# PulseFit.net
KiCad netlist of a schematic drawn in EAGLE
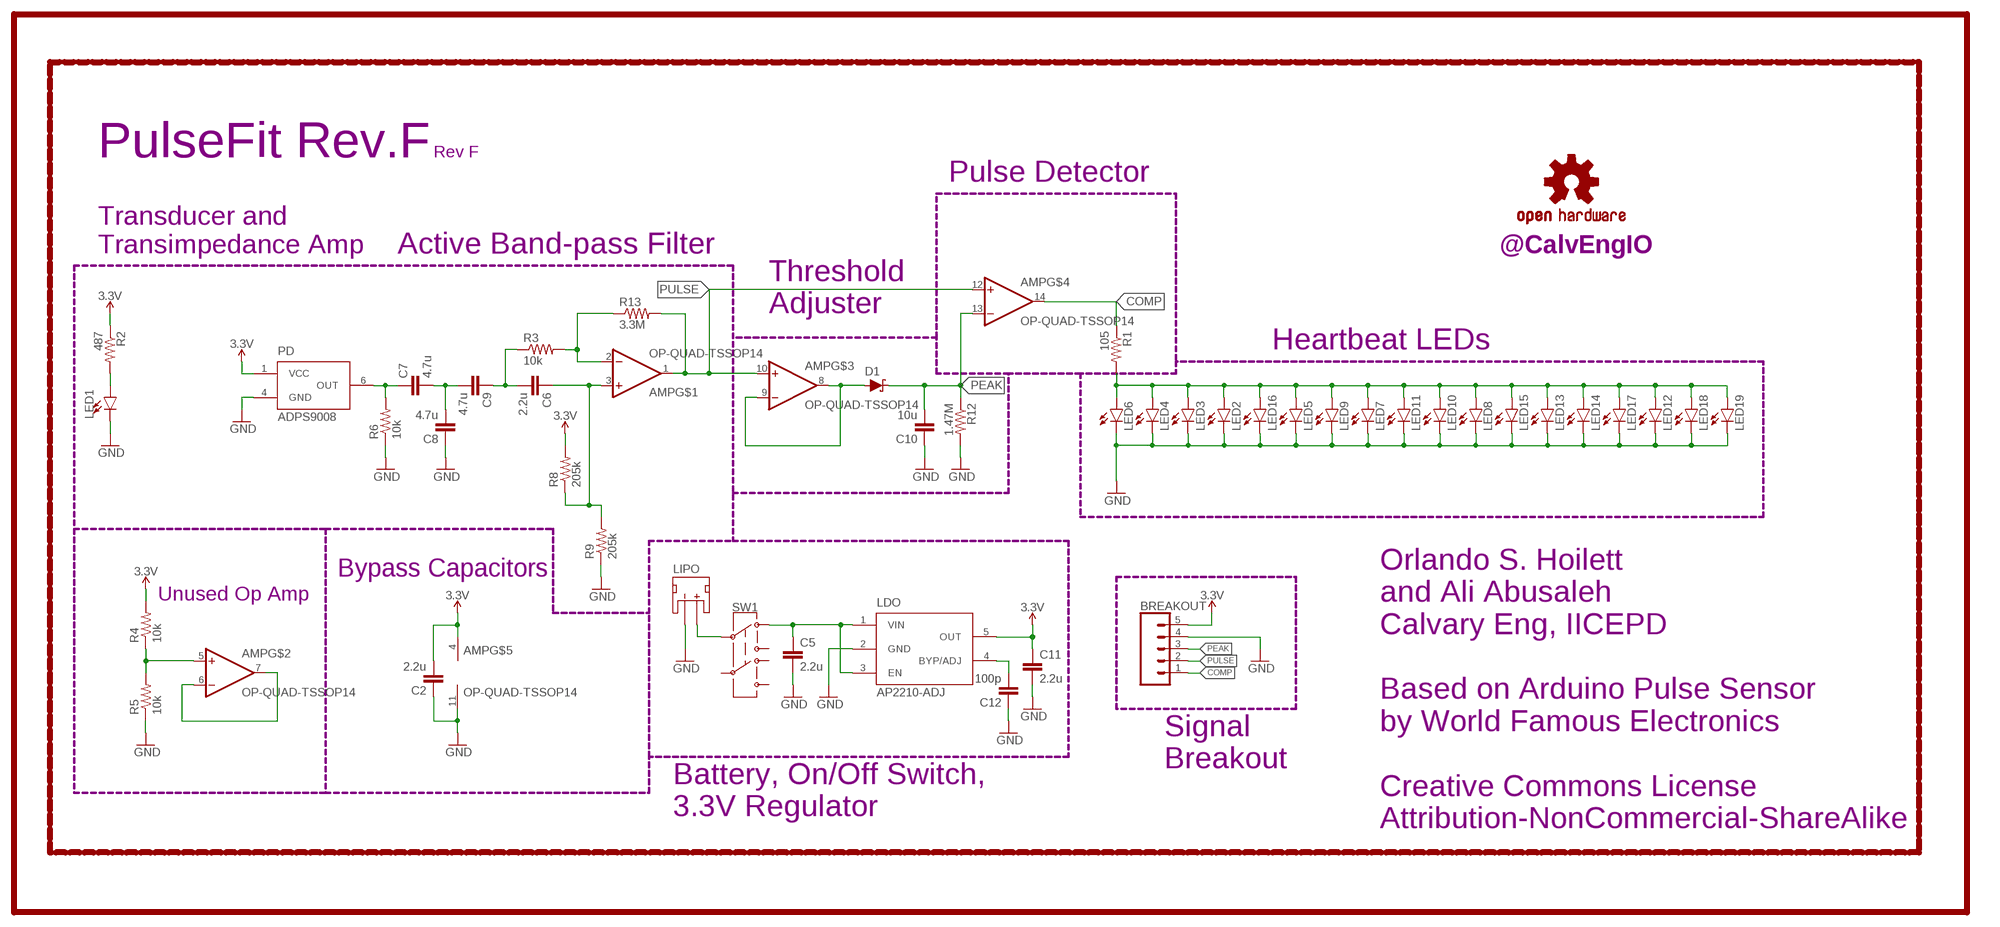
[diagram p0: schematic, sheet 1]

(export (version "E")
  (design (tool "Eeschema 10.0.6"))
  (components
    (comp (ref "AMP")
      (value "OP-QUAD-TSSOP14")
      (footprint "eagle-import:TSSOP14")
      (libsource (lib "eagle-import") (part "OP-QUAD-TSSOP14"))
    )
    (comp (ref "BREAKOUT")
      (value "CONN_05NO_SILK")
      (footprint "eagle-import:1X05_NO_SILK")
      (libsource (lib "eagle-import") (part "CONN_05NO_SILK"))
    )
    (comp (ref "C2")
      (value "2.2u")
      (footprint "eagle-import:C0402")
      (libsource (lib "eagle-import") (part "CAPACITOR0402"))
    )
    (comp (ref "C5")
      (value "2.2u")
      (footprint "eagle-import:C0603")
      (libsource (lib "eagle-import") (part "CAPACITOR0603"))
    )
    (comp (ref "C6")
      (value "2.2u")
      (footprint "eagle-import:C0603")
      (libsource (lib "eagle-import") (part "CAPACITOR0603"))
    )
    (comp (ref "C7")
      (value "4.7u")
      (footprint "eagle-import:C0603")
      (libsource (lib "eagle-import") (part "CAPACITOR0603"))
    )
    (comp (ref "C8")
      (value "4.7u")
      (footprint "eagle-import:C0603")
      (libsource (lib "eagle-import") (part "CAPACITOR0603"))
    )
    (comp (ref "C9")
      (value "4.7u")
      (footprint "eagle-import:C0603")
      (libsource (lib "eagle-import") (part "CAPACITOR0603"))
    )
    (comp (ref "C10")
      (value "10u")
      (footprint "eagle-import:C0805")
      (libsource (lib "eagle-import") (part "CAPACITOR0805"))
    )
    (comp (ref "C11")
      (value "2.2u")
      (footprint "eagle-import:C0603")
      (libsource (lib "eagle-import") (part "CAPACITOR0603"))
    )
    (comp (ref "C12")
      (value "100p")
      (footprint "eagle-import:C0402")
      (libsource (lib "eagle-import") (part "CAPACITOR0402"))
    )
    (comp (ref "D1")
      (value "SCHOTTKY-USC")
      (footprint "eagle-import:USC")
      (libsource (lib "eagle-import") (part "SCHOTTKY-USC"))
    )
    (comp (ref "LDO")
      (value "AP2210-ADJ")
      (footprint "eagle-import:SOT23-5")
      (libsource (lib "eagle-import") (part "AP2210-ADJ"))
    )
    (comp (ref "LED1")
      (value "LEDZ-BEND")
      (footprint "eagle-import:2-SMD.Z-BEND")
      (libsource (lib "eagle-import") (part "LEDZ-BEND"))
    )
    (comp (ref "LED2")
      (value "LED5MM")
      (footprint "eagle-import:LED5MM")
      (libsource (lib "eagle-import") (part "SparkFun-LED_LED5MM"))
    )
    (comp (ref "LED3")
      (value "LED5MM")
      (footprint "eagle-import:LED5MM")
      (libsource (lib "eagle-import") (part "SparkFun-LED_LED5MM"))
    )
    (comp (ref "LED4")
      (value "LED5MM")
      (footprint "eagle-import:LED5MM")
      (libsource (lib "eagle-import") (part "SparkFun-LED_LED5MM"))
    )
    (comp (ref "LED5")
      (value "LED5MM")
      (footprint "eagle-import:LED5MM")
      (libsource (lib "eagle-import") (part "SparkFun-LED_LED5MM"))
    )
    (comp (ref "LED6")
      (value "LED5MM")
      (footprint "eagle-import:LED5MM")
      (libsource (lib "eagle-import") (part "SparkFun-LED_LED5MM"))
    )
    (comp (ref "LED7")
      (value "LED5MM")
      (footprint "eagle-import:LED5MM")
      (libsource (lib "eagle-import") (part "SparkFun-LED_LED5MM"))
    )
    (comp (ref "LED8")
      (value "LED5MM")
      (footprint "eagle-import:LED5MM")
      (libsource (lib "eagle-import") (part "SparkFun-LED_LED5MM"))
    )
    (comp (ref "LED9")
      (value "LED5MM")
      (footprint "eagle-import:LED5MM")
      (libsource (lib "eagle-import") (part "SparkFun-LED_LED5MM"))
    )
    (comp (ref "LED10")
      (value "LED5MM")
      (footprint "eagle-import:LED5MM")
      (libsource (lib "eagle-import") (part "SparkFun-LED_LED5MM"))
    )
    (comp (ref "LED11")
      (value "LED5MM")
      (footprint "eagle-import:LED5MM")
      (libsource (lib "eagle-import") (part "SparkFun-LED_LED5MM"))
    )
    (comp (ref "LED12")
      (value "LED5MM")
      (footprint "eagle-import:LED5MM")
      (libsource (lib "eagle-import") (part "SparkFun-LED_LED5MM"))
    )
    (comp (ref "LED13")
      (value "LED5MM")
      (footprint "eagle-import:LED5MM")
      (libsource (lib "eagle-import") (part "SparkFun-LED_LED5MM"))
    )
    (comp (ref "LED14")
      (value "LED5MM")
      (footprint "eagle-import:LED5MM")
      (libsource (lib "eagle-import") (part "SparkFun-LED_LED5MM"))
    )
    (comp (ref "LED15")
      (value "LED5MM")
      (footprint "eagle-import:LED5MM")
      (libsource (lib "eagle-import") (part "SparkFun-LED_LED5MM"))
    )
    (comp (ref "LED16")
      (value "LED5MM")
      (footprint "eagle-import:LED5MM")
      (libsource (lib "eagle-import") (part "SparkFun-LED_LED5MM"))
    )
    (comp (ref "LED17")
      (value "LED5MM")
      (footprint "eagle-import:LED5MM")
      (libsource (lib "eagle-import") (part "SparkFun-LED_LED5MM"))
    )
    (comp (ref "LED18")
      (value "LED5MM")
      (footprint "eagle-import:LED5MM")
      (libsource (lib "eagle-import") (part "SparkFun-LED_LED5MM"))
    )
    (comp (ref "LED19")
      (value "LED5MM")
      (footprint "eagle-import:LED5MM")
      (libsource (lib "eagle-import") (part "SparkFun-LED_LED5MM"))
    )
    (comp (ref "LIPO")
      (value "JST_2MM_MALE")
      (footprint "eagle-import:JST-2-SMD")
      (libsource (lib "eagle-import") (part "JST_2MM_MALE"))
    )
    (comp (ref "LOGO1")
      (value "OSHW-LOGOS")
      (footprint "eagle-import:OSHW-LOGO-S")
      (libsource (lib "eagle-import") (part "OSHW-LOGOS"))
    )
    (comp (ref "PD")
      (value "ADPS9008")
      (footprint "eagle-import:6-PIN.CHIPLED")
      (libsource (lib "eagle-import") (part "ADPS9008"))
    )
    (comp (ref "R1")
      (value "105")
      (footprint "eagle-import:R0402")
      (libsource (lib "eagle-import") (part "RESISTOR0402"))
    )
    (comp (ref "R2")
      (value "487")
      (footprint "eagle-import:R0402")
      (libsource (lib "eagle-import") (part "RESISTOR0402"))
    )
    (comp (ref "R3")
      (value "10k")
      (footprint "eagle-import:R0402")
      (libsource (lib "eagle-import") (part "RESISTOR0402"))
    )
    (comp (ref "R4")
      (value "10k")
      (footprint "eagle-import:R0402")
      (libsource (lib "eagle-import") (part "RESISTOR0402"))
    )
    (comp (ref "R5")
      (value "10k")
      (footprint "eagle-import:R0402")
      (libsource (lib "eagle-import") (part "RESISTOR0402"))
    )
    (comp (ref "R6")
      (value "10k")
      (footprint "eagle-import:R0402")
      (libsource (lib "eagle-import") (part "RESISTOR0402"))
    )
    (comp (ref "R8")
      (value "205k")
      (footprint "eagle-import:R0402")
      (libsource (lib "eagle-import") (part "RESISTOR0402"))
    )
    (comp (ref "R9")
      (value "205k")
      (footprint "eagle-import:R0402")
      (libsource (lib "eagle-import") (part "RESISTOR0402"))
    )
    (comp (ref "R12")
      (value "1.47M")
      (footprint "eagle-import:R0402")
      (libsource (lib "eagle-import") (part "RESISTOR0402"))
    )
    (comp (ref "R13")
      (value "3.3M")
      (footprint "eagle-import:R0402")
      (libsource (lib "eagle-import") (part "RESISTOR0402"))
    )
    (comp (ref "SW1")
      (value "SWITCH.JS202011JCQN")
      (footprint "eagle-import:SWITCH.00")
      (libsource (lib "eagle-import") (part "SWITCH.JS202011JCQN"))
    )
    (comp (ref "U$1")
      (value "CALVENGIO_HANDLEHANDLE.05")
      (footprint "eagle-import:CALVENGIO_HANDLE.05")
      (libsource (lib "eagle-import") (part "CALVENGIO_HANDLEHANDLE.05"))
    )
    (comp (ref "U$2")
      (value "REVISION.F")
      (footprint "eagle-import:REV.F")
      (libsource (lib "eagle-import") (part "REVISION.F"))
    )
  )
  (nets
    (net (code "1") (name "3.3V") (class "Default")
      (node (ref "AMP") (pin "4") (pinfunction "V+_4") (pintype "power_in"))
      (node (ref "BREAKOUT") (pin "5") (pinfunction "5_5") (pintype "passive"))
      (node (ref "C11") (pin "1") (pinfunction "1_1") (pintype "passive"))
      (node (ref "C2") (pin "2") (pinfunction "2_2") (pintype "passive"))
      (node (ref "LDO") (pin "5") (pinfunction "OUT_5") (pintype "bidirectional"))
      (node (ref "PD") (pin "1") (pinfunction "VCC_1") (pintype "bidirectional"))
      (node (ref "R2") (pin "1") (pinfunction "1_1") (pintype "passive"))
      (node (ref "R4") (pin "2") (pinfunction "2_2") (pintype "passive"))
      (node (ref "R8") (pin "2") (pinfunction "2_2") (pintype "passive"))
    )
    (net (code "2") (name "COMP") (class "Default")
      (node (ref "AMP") (pin "14") (pinfunction "OUT_14") (pintype "output"))
      (node (ref "BREAKOUT") (pin "1") (pinfunction "1_1") (pintype "passive"))
      (node (ref "R1") (pin "1") (pinfunction "1_1") (pintype "passive"))
    )
    (net (code "3") (name "GND") (class "Default")
      (node (ref "AMP") (pin "11") (pinfunction "V-_11") (pintype "power_in"))
      (node (ref "BREAKOUT") (pin "4") (pinfunction "4_4") (pintype "passive"))
      (node (ref "C10") (pin "1") (pinfunction "1_1") (pintype "passive"))
      (node (ref "C11") (pin "2") (pinfunction "2_2") (pintype "passive"))
      (node (ref "C12") (pin "1") (pinfunction "1_1") (pintype "passive"))
      (node (ref "C2") (pin "1") (pinfunction "1_1") (pintype "passive"))
      (node (ref "C5") (pin "2") (pinfunction "2_2") (pintype "passive"))
      (node (ref "C8") (pin "1") (pinfunction "1_1") (pintype "passive"))
      (node (ref "LDO") (pin "2") (pinfunction "GND_2") (pintype "bidirectional"))
      (node (ref "LED1") (pin "-") (pinfunction "C_-") (pintype "passive"))
      (node (ref "LED10") (pin "K") (pinfunction "C_K") (pintype "passive"))
      (node (ref "LED11") (pin "K") (pinfunction "C_K") (pintype "passive"))
      (node (ref "LED12") (pin "K") (pinfunction "C_K") (pintype "passive"))
      (node (ref "LED13") (pin "K") (pinfunction "C_K") (pintype "passive"))
      (node (ref "LED14") (pin "K") (pinfunction "C_K") (pintype "passive"))
      (node (ref "LED15") (pin "K") (pinfunction "C_K") (pintype "passive"))
      (node (ref "LED16") (pin "K") (pinfunction "C_K") (pintype "passive"))
      (node (ref "LED17") (pin "K") (pinfunction "C_K") (pintype "passive"))
      (node (ref "LED18") (pin "K") (pinfunction "C_K") (pintype "passive"))
      (node (ref "LED19") (pin "K") (pinfunction "C_K") (pintype "passive"))
      (node (ref "LED2") (pin "K") (pinfunction "C_K") (pintype "passive"))
      (node (ref "LED3") (pin "K") (pinfunction "C_K") (pintype "passive"))
      (node (ref "LED4") (pin "K") (pinfunction "C_K") (pintype "passive"))
      (node (ref "LED5") (pin "K") (pinfunction "C_K") (pintype "passive"))
      (node (ref "LED6") (pin "K") (pinfunction "C_K") (pintype "passive"))
      (node (ref "LED7") (pin "K") (pinfunction "C_K") (pintype "passive"))
      (node (ref "LED8") (pin "K") (pinfunction "C_K") (pintype "passive"))
      (node (ref "LED9") (pin "K") (pinfunction "C_K") (pintype "passive"))
      (node (ref "LIPO") (pin "1") (pinfunction "-_1") (pintype "bidirectional"))
      (node (ref "PD") (pin "4") (pinfunction "GND_4") (pintype "bidirectional"))
      (node (ref "R12") (pin "2") (pinfunction "2_2") (pintype "passive"))
      (node (ref "R5") (pin "1") (pinfunction "1_1") (pintype "passive"))
      (node (ref "R6") (pin "1") (pinfunction "1_1") (pintype "passive"))
      (node (ref "R9") (pin "1") (pinfunction "1_1") (pintype "passive"))
    )
    (net (code "4") (name "Net-(AMPA-+IN)") (class "Default")
      (node (ref "AMP") (pin "3") (pinfunction "+IN_3") (pintype "input"))
      (node (ref "C6") (pin "1") (pinfunction "1_1") (pintype "passive"))
      (node (ref "R8") (pin "1") (pinfunction "1_1") (pintype "passive"))
      (node (ref "R9") (pin "2") (pinfunction "2_2") (pintype "passive"))
    )
    (net (code "5") (name "Net-(AMPA--IN)") (class "Default")
      (node (ref "AMP") (pin "2") (pinfunction "-IN_2") (pintype "input"))
      (node (ref "R13") (pin "1") (pinfunction "1_1") (pintype "passive"))
      (node (ref "R3") (pin "2") (pinfunction "2_2") (pintype "passive"))
    )
    (net (code "6") (name "Net-(AMPB-+IN)") (class "Default")
      (node (ref "AMP") (pin "5") (pinfunction "+IN_5") (pintype "input"))
      (node (ref "R4") (pin "1") (pinfunction "1_1") (pintype "passive"))
      (node (ref "R5") (pin "2") (pinfunction "2_2") (pintype "passive"))
    )
    (net (code "7") (name "Net-(AMPB--IN)") (class "Default")
      (node (ref "AMP") (pin "6") (pinfunction "-IN_6") (pintype "input"))
      (node (ref "AMP") (pin "7") (pinfunction "OUT_7") (pintype "output"))
    )
    (net (code "8") (name "Net-(AMPC--IN)") (class "Default")
      (node (ref "AMP") (pin "8") (pinfunction "OUT_8") (pintype "output"))
      (node (ref "AMP") (pin "9") (pinfunction "-IN_9") (pintype "input"))
      (node (ref "D1") (pin "+") (pinfunction "A_+") (pintype "passive"))
    )
    (net (code "9") (name "Net-(C6-Pad2)") (class "Default")
      (node (ref "C6") (pin "2") (pinfunction "2_2") (pintype "passive"))
      (node (ref "C9") (pin "1") (pinfunction "1_1") (pintype "passive"))
      (node (ref "R3") (pin "1") (pinfunction "1_1") (pintype "passive"))
    )
    (net (code "10") (name "Net-(C7-Pad2)") (class "Default")
      (node (ref "C7") (pin "2") (pinfunction "2_2") (pintype "passive"))
      (node (ref "C8") (pin "2") (pinfunction "2_2") (pintype "passive"))
      (node (ref "C9") (pin "2") (pinfunction "2_2") (pintype "passive"))
    )
    (net (code "11") (name "Net-(LDO-BYP{slash}ADJ)") (class "Default")
      (node (ref "C12") (pin "2") (pinfunction "2_2") (pintype "passive"))
      (node (ref "LDO") (pin "4") (pinfunction "BYP/ADJ_4") (pintype "bidirectional"))
    )
    (net (code "12") (name "Net-(LDO-EN)") (class "Default")
      (node (ref "C5") (pin "1") (pinfunction "1_1") (pintype "passive"))
      (node (ref "LDO") (pin "1") (pinfunction "VIN_1") (pintype "bidirectional"))
      (node (ref "LDO") (pin "3") (pinfunction "EN_3") (pintype "bidirectional"))
      (node (ref "SW1") (pin "1") (pinfunction "1_1") (pintype "bidirectional"))
    )
    (net (code "13") (name "Net-(LED1-A)") (class "Default")
      (node (ref "LED1") (pin "+") (pinfunction "A_+") (pintype "passive"))
      (node (ref "R2") (pin "2") (pinfunction "2_2") (pintype "passive"))
    )
    (net (code "14") (name "Net-(LED10-PadA)") (class "Default")
      (node (ref "LED10") (pin "A") (pinfunction "A_A") (pintype "passive"))
      (node (ref "LED11") (pin "A") (pinfunction "A_A") (pintype "passive"))
      (node (ref "LED12") (pin "A") (pinfunction "A_A") (pintype "passive"))
      (node (ref "LED13") (pin "A") (pinfunction "A_A") (pintype "passive"))
      (node (ref "LED14") (pin "A") (pinfunction "A_A") (pintype "passive"))
      (node (ref "LED15") (pin "A") (pinfunction "A_A") (pintype "passive"))
      (node (ref "LED16") (pin "A") (pinfunction "A_A") (pintype "passive"))
      (node (ref "LED17") (pin "A") (pinfunction "A_A") (pintype "passive"))
      (node (ref "LED18") (pin "A") (pinfunction "A_A") (pintype "passive"))
      (node (ref "LED19") (pin "A") (pinfunction "A_A") (pintype "passive"))
      (node (ref "LED2") (pin "A") (pinfunction "A_A") (pintype "passive"))
      (node (ref "LED3") (pin "A") (pinfunction "A_A") (pintype "passive"))
      (node (ref "LED4") (pin "A") (pinfunction "A_A") (pintype "passive"))
      (node (ref "LED5") (pin "A") (pinfunction "A_A") (pintype "passive"))
      (node (ref "LED6") (pin "A") (pinfunction "A_A") (pintype "passive"))
      (node (ref "LED7") (pin "A") (pinfunction "A_A") (pintype "passive"))
      (node (ref "LED8") (pin "A") (pinfunction "A_A") (pintype "passive"))
      (node (ref "LED9") (pin "A") (pinfunction "A_A") (pintype "passive"))
      (node (ref "R1") (pin "2") (pinfunction "2_2") (pintype "passive"))
    )
    (net (code "15") (name "Net-(LIPO-+)") (class "Default")
      (node (ref "LIPO") (pin "2") (pinfunction "+_2") (pintype "bidirectional"))
      (node (ref "SW1") (pin "2") (pinfunction "2_2") (pintype "bidirectional"))
    )
    (net (code "16") (name "Net-(PD-OUT)") (class "Default")
      (node (ref "C7") (pin "1") (pinfunction "1_1") (pintype "passive"))
      (node (ref "PD") (pin "6") (pinfunction "OUT_6") (pintype "bidirectional"))
      (node (ref "R6") (pin "2") (pinfunction "2_2") (pintype "passive"))
    )
    (net (code "17") (name "PEAK") (class "Default")
      (node (ref "AMP") (pin "13") (pinfunction "-IN_13") (pintype "input"))
      (node (ref "BREAKOUT") (pin "3") (pinfunction "3_3") (pintype "passive"))
      (node (ref "C10") (pin "2") (pinfunction "2_2") (pintype "passive"))
      (node (ref "D1") (pin "-") (pinfunction "C_-") (pintype "passive"))
      (node (ref "R12") (pin "1") (pinfunction "1_1") (pintype "passive"))
    )
    (net (code "18") (name "PULSE") (class "Default")
      (node (ref "AMP") (pin "1") (pinfunction "OUT_1") (pintype "output"))
      (node (ref "AMP") (pin "10") (pinfunction "+IN_10") (pintype "input"))
      (node (ref "AMP") (pin "12") (pinfunction "+IN_12") (pintype "input"))
      (node (ref "BREAKOUT") (pin "2") (pinfunction "2_2") (pintype "passive"))
      (node (ref "R13") (pin "2") (pinfunction "2_2") (pintype "passive"))
    )
    (net (code "19") (name "unconnected-(LIPO-PAD1-PadNC1)") (class "Default")
      (node (ref "LIPO") (pin "NC1") (pinfunction "PAD1_NC1") (pintype "bidirectional"))
    )
    (net (code "20") (name "unconnected-(LIPO-PAD2-PadNC2)") (class "Default")
      (node (ref "LIPO") (pin "NC2") (pinfunction "PAD2_NC2") (pintype "bidirectional"))
    )
    (net (code "21") (name "unconnected-(SW1-Pad3)") (class "Default")
      (node (ref "SW1") (pin "3") (pinfunction "3_3") (pintype "bidirectional"))
    )
    (net (code "22") (name "unconnected-(SW1-Pad5)") (class "Default")
      (node (ref "SW1") (pin "5") (pinfunction "5_5") (pintype "bidirectional"))
    )
    (net (code "23") (name "unconnected-(SW1-Pad6)") (class "Default")
      (node (ref "SW1") (pin "6") (pinfunction "6_6") (pintype "bidirectional"))
    )
    (net (code "24") (name "unconnected-(SW1-Pad7)") (class "Default")
      (node (ref "SW1") (pin "7") (pinfunction "7_7") (pintype "bidirectional"))
    )
  )
)
